# design.net
KiCad netlist of a schematic drawn in Altium Designer
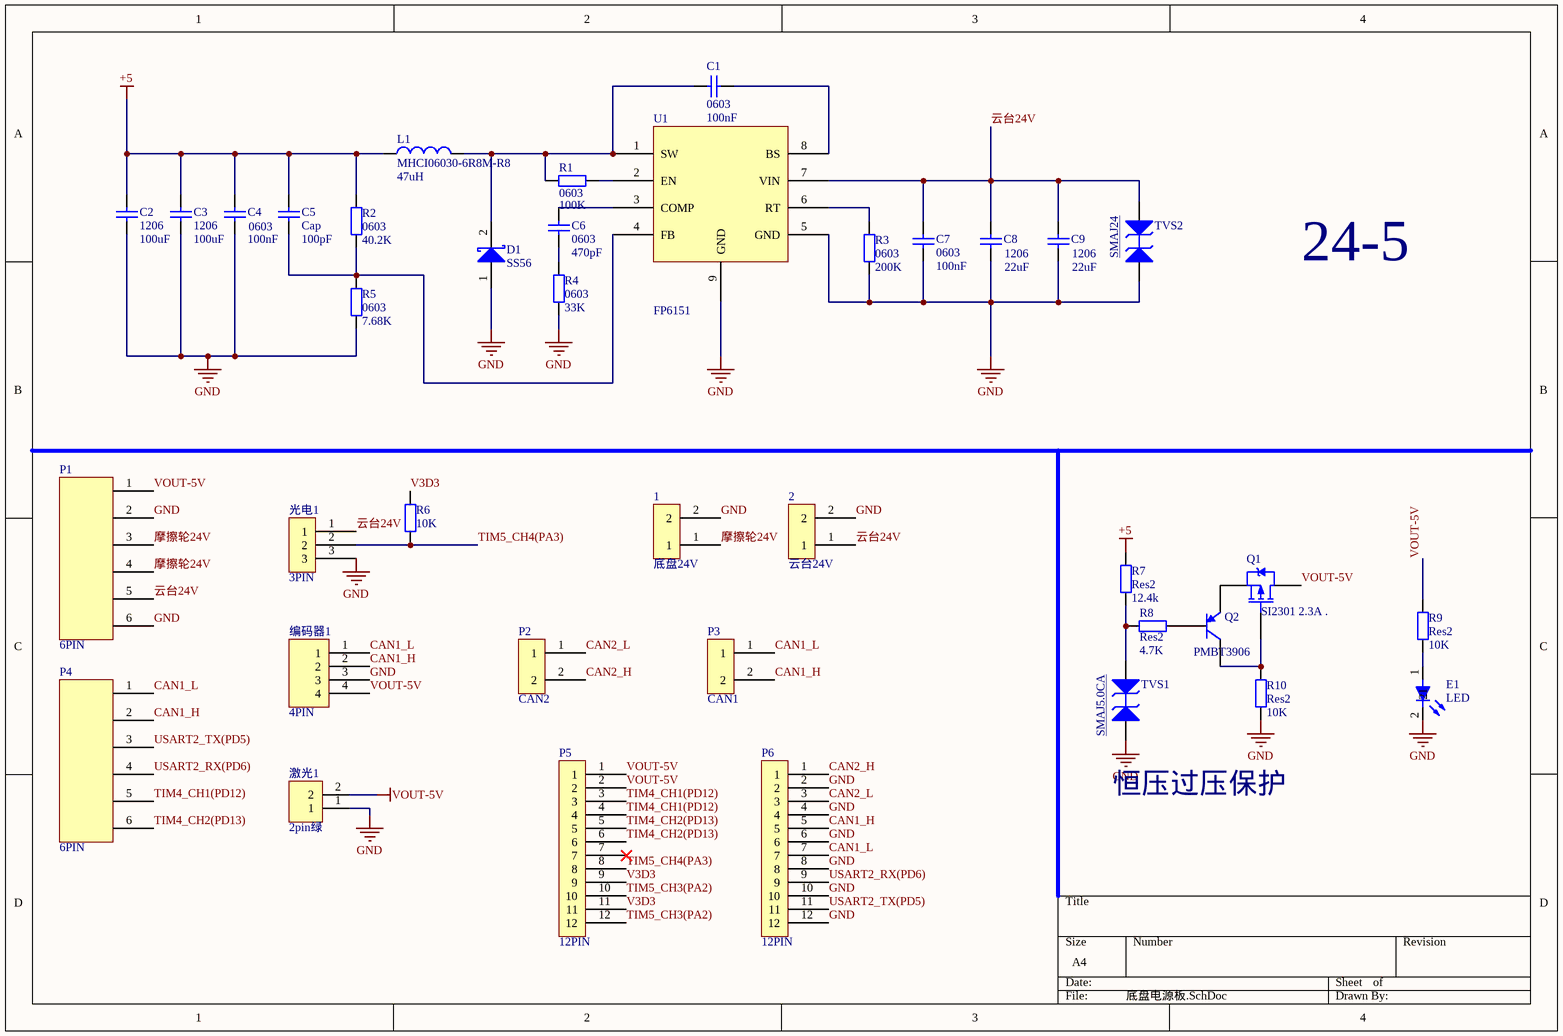
[diagram p0: 底盘电源板.SchDoc]

(export (version "E")
  (design (tool "Eeschema 10.0.6"))
  (components
    (comp (ref "1") (value "底盘24V") (footprint "XT30") (libsource (lib "PP_SCHlib_Altium") (part "2PIN")))
    (comp (ref "2") (value "云台24V") (footprint "XT30") (libsource (lib "PP_SCHlib_Altium") (part "2PIN")))
    (comp (ref "C1")
      (value "0603")
      (footprint "C0603")
      (description "Capacitor")
      (fields (field (name "0603") "100nF") (field (name "PUBLISHER") "Altium Limited"))
      (libsource (lib "Miscellaneous Devices") (part "Cap"))
    )
    (comp (ref "C2")
      (value "1206")
      (footprint "C1206")
      (description "Capacitor")
      (fields (field (name "ALTIUM_VALUE") "100uF") (field (name "PUBLISHER") "Altium Limited"))
      (libsource (lib "Miscellaneous Devices") (part "Cap"))
    )
    (comp (ref "C3")
      (value "1206")
      (footprint "C1206")
      (description "Capacitor")
      (fields (field (name "ALTIUM_VALUE") "100uF") (field (name "PUBLISHER") "Altium Limited"))
      (libsource (lib "Miscellaneous Devices") (part "Cap"))
    )
    (comp (ref "C4")
      (value "0603")
      (footprint "C0603")
      (description "Capacitor")
      (fields (field (name "ALTIUM_VALUE") "100nF") (field (name "PUBLISHER") "Altium Limited"))
      (libsource (lib "Miscellaneous Devices") (part "Cap"))
    )
    (comp (ref "C5")
      (value "Cap")
      (footprint "C0603")
      (description "Capacitor")
      (fields (field (name "ALTIUM_VALUE") "100pF") (field (name "PUBLISHER") "Altium Limited"))
      (libsource (lib "Miscellaneous Devices") (part "Cap"))
    )
    (comp (ref "C6")
      (value "0603")
      (footprint "C0603")
      (description "Capacitor")
      (fields (field (name "ALTIUM_VALUE") "470pF") (field (name "PUBLISHER") "Altium Limited"))
      (libsource (lib "Miscellaneous Devices") (part "Cap"))
    )
    (comp (ref "C7")
      (value "0603")
      (footprint "C0603")
      (description "Capacitor")
      (fields (field (name "0603") "100nF") (field (name "PUBLISHER") "Altium Limited"))
      (libsource (lib "Miscellaneous Devices") (part "Cap"))
    )
    (comp (ref "C8")
      (value "1206")
      (footprint "C1206")
      (description "Capacitor")
      (fields (field (name "ALTIUM_VALUE") "22uF") (field (name "PUBLISHER") "Altium Limited"))
      (libsource (lib "Miscellaneous Devices") (part "Cap"))
    )
    (comp (ref "C9")
      (value "1206")
      (footprint "C1206")
      (description "Capacitor")
      (fields (field (name "ALTIUM_VALUE") "22uF") (field (name "PUBLISHER") "Altium Limited"))
      (libsource (lib "Miscellaneous Devices") (part "Cap"))
    )
    (comp (ref "D1")
      (value "D-Schottky")
      (footprint "肖特基")
      (description "肖特基二极管")
      (fields (field (name "TYPE") "SS56") (field (name "PUBLISHER") "Altium Limited"))
      (libsource (lib "更多原理图库") (part "D-Schottky"))
    )
    (comp (ref "E1")
      (value "LED")
      (footprint "LED")
      (description "Typical RED, GREEN, YELLOW, AMBER GaAs LED")
      (fields (field (name "PUBLISHER") "Altium Limited"))
      (libsource (lib "PP_SCHlib_Altium") (part "LED"))
    )
    (comp (ref "L1")
      (value "MHCI06030-6R8M-R8")
      (footprint "L")
      (description "Inductor")
      (fields (field (name "ALTIUM_VALUE") "47uH") (field (name "PUBLISHER") "Altium Limited"))
      (libsource (lib "Miscellaneous Devices") (part "Inductor"))
    )
    (comp (ref "P1") (value "6PIN") (footprint "6PIN") (libsource (lib "PP_SCHlib_Altium") (part "6PIN")))
    (comp (ref "P2") (value "CAN2") (footprint "CAN") (libsource (lib "") (part "2PIN_1")))
    (comp (ref "P3") (value "CAN1") (footprint "CAN") (libsource (lib "") (part "2PIN_1")))
    (comp (ref "P4") (value "6PIN") (footprint "6PIN") (libsource (lib "PP_SCHlib_Altium") (part "6PIN")))
    (comp (ref "P5") (value "12PIN") (footprint "12pin") (libsource (lib "更多原理图库") (part "12PIN")))
    (comp (ref "P6") (value "12PIN") (footprint "12pin") (libsource (lib "更多原理图库") (part "12PIN")))
    (comp (ref "Q1")
      (value "SI2301 2.3A .")
      (footprint "SOT3")
      (description "P-Channel Power MOSFET")
      (fields (field (name "PUBLISHER") "Altium Limited"))
      (libsource (lib "Miscellaneous Devices") (part "PMOS-2"))
    )
    (comp (ref "Q2")
      (value "PMBT3906")
      (footprint "SOT3")
      (description "PNP Bipolar Transistor")
      (fields (field (name "PUBLISHER") "Altium Limited"))
      (libsource (lib "Miscellaneous Devices") (part "PNP"))
    )
    (comp (ref "R1")
      (value "0603")
      (footprint "R0603")
      (description "Resistor")
      (fields (field (name "0603") "100K") (field (name "PUBLISHER") "Altium Limited"))
      (libsource (lib "") (part "Res2_1"))
    )
    (comp (ref "R2")
      (value "0603")
      (footprint "R0603")
      (description "Resistor")
      (fields (field (name "ALTIUM_VALUE") "40.2K") (field (name "PUBLISHER") "Altium Limited"))
      (libsource (lib "Miscellaneous Devices") (part "Res2"))
    )
    (comp (ref "R3")
      (value "0603")
      (footprint "R0603")
      (description "Resistor")
      (fields (field (name "0603") "200K") (field (name "PUBLISHER") "Altium Limited"))
      (libsource (lib "Miscellaneous Devices") (part "Res2"))
    )
    (comp (ref "R4")
      (value "0603")
      (footprint "R0603")
      (description "Resistor")
      (fields (field (name "ALTIUM_VALUE") "33K") (field (name "PUBLISHER") "Altium Limited"))
      (libsource (lib "Miscellaneous Devices") (part "Res2"))
    )
    (comp (ref "R5")
      (value "0603")
      (footprint "R0603")
      (description "Resistor")
      (fields (field (name "ALTIUM_VALUE") "7.68K") (field (name "PUBLISHER") "Altium Limited"))
      (libsource (lib "Miscellaneous Devices") (part "Res2"))
    )
    (comp (ref "R6")
      (value "10K")
      (footprint "0805")
      (description "贴片电阻")
      (fields (field (name "Comment") "Res1") (field (name "PUBLISHER") "Altium Limited"))
      (libsource (lib "stm32test") (part "Res1"))
    )
    (comp (ref "R7")
      (value "Res2")
      (footprint "R0603")
      (description "Resistor")
      (fields (field (name "ALTIUM_VALUE") "12.4k") (field (name "PUBLISHER") "Altium Limited"))
      (libsource (lib "Miscellaneous Devices") (part "Res2"))
    )
    (comp (ref "R8")
      (value "Res2")
      (footprint "R0603")
      (description "Resistor")
      (fields (field (name "ALTIUM_VALUE") "4.7K") (field (name "PUBLISHER") "Altium Limited"))
      (libsource (lib "") (part "Res2_2"))
    )
    (comp (ref "R9")
      (value "Res2")
      (footprint "R0603")
      (description "Resistor")
      (fields (field (name "ALTIUM_VALUE") "10K") (field (name "PUBLISHER") "Altium Limited"))
      (libsource (lib "") (part "Res2_3"))
    )
    (comp (ref "R10")
      (value "Res2")
      (footprint "R0603")
      (description "Resistor")
      (fields (field (name "ALTIUM_VALUE") "10K") (field (name "PUBLISHER") "Altium Limited"))
      (libsource (lib "Miscellaneous Devices") (part "Res2"))
    )
    (comp (ref "TVS1")
      (value "SMAJ5.0CA")
      (footprint "SMAJ5.0")
      (libsource (lib "VL53L0X激光测距传感器模块") (part "TVS"))
    )
    (comp (ref "TVS2")
      (value "SMAJ24")
      (footprint "SMAJ24")
      (libsource (lib "VL53L0X激光测距传感器模块") (part "TVS"))
    )
    (comp (ref "U1") (value "FP6151") (footprint "FP") (libsource (lib "Schlib1") (part "FP6151")))
    (comp (ref "光电1") (value "3PIN") (footprint "光电") (libsource (lib "PP_SCHlib_Altium") (part "3PIN")))
    (comp (ref "激光1")
      (value "2pin绿")
      (footprint "2pin")
      (description "Molex-53261-0871")
      (fields (field (name "PUBLISHER") "Altium Limited"))
      (libsource (lib "通用板") (part "Molex-53398-0271"))
    )
    (comp (ref "编码器1") (value "4PIN") (footprint "编码器") (libsource (lib "PP_SCHlib_Altium") (part "4PIN")))
  )
  (nets
    (net (code "1") (name "+5") (class "Default")
      (node (ref "C2") (pin "2") (pinfunction "2_2") (pintype "passive"))
      (node (ref "C3") (pin "2") (pinfunction "2_2") (pintype "passive"))
      (node (ref "C4") (pin "2") (pinfunction "2_2") (pintype "passive"))
      (node (ref "C5") (pin "2") (pinfunction "2_2") (pintype "passive"))
      (node (ref "L1") (pin "1") (pinfunction "1_1") (pintype "passive"))
      (node (ref "R2") (pin "2") (pinfunction "2_2") (pintype "passive"))
      (node (ref "R7") (pin "2") (pinfunction "2_2") (pintype "passive"))
    )
    (net (code "2") (name "/CAN1_H") (class "Default")
      (node (ref "P3") (pin "2") (pinfunction "2_2") (pintype "passive"))
      (node (ref "P4") (pin "2") (pinfunction "2_2") (pintype "passive"))
      (node (ref "P6") (pin "5") (pinfunction "5_5") (pintype "passive"))
      (node (ref "编码器1") (pin "2") (pinfunction "2_2") (pintype "passive"))
    )
    (net (code "3") (name "/CAN1_L") (class "Default")
      (node (ref "P3") (pin "1") (pinfunction "1_1") (pintype "passive"))
      (node (ref "P4") (pin "1") (pinfunction "1_1") (pintype "passive"))
      (node (ref "P6") (pin "7") (pinfunction "7_7") (pintype "passive"))
      (node (ref "编码器1") (pin "1") (pinfunction "1_1") (pintype "passive"))
    )
    (net (code "4") (name "/CAN2_H") (class "Default")
      (node (ref "P2") (pin "2") (pinfunction "2_2") (pintype "passive"))
      (node (ref "P6") (pin "1") (pinfunction "1_1") (pintype "passive"))
    )
    (net (code "5") (name "/CAN2_L") (class "Default")
      (node (ref "P2") (pin "1") (pinfunction "1_1") (pintype "passive"))
      (node (ref "P6") (pin "3") (pinfunction "3_3") (pintype "passive"))
    )
    (net (code "6") (name "/TIM4_CH1(PD12)") (class "Default")
      (node (ref "P4") (pin "5") (pinfunction "5_5") (pintype "passive"))
      (node (ref "P5") (pin "3") (pinfunction "3_3") (pintype "passive"))
      (node (ref "P5") (pin "4") (pinfunction "4_4") (pintype "passive"))
    )
    (net (code "7") (name "/TIM4_CH2(PD13)") (class "Default")
      (node (ref "P4") (pin "6") (pinfunction "6_6") (pintype "passive"))
      (node (ref "P5") (pin "5") (pinfunction "5_5") (pintype "passive"))
      (node (ref "P5") (pin "6") (pinfunction "6_6") (pintype "passive"))
    )
    (net (code "8") (name "/TIM5_CH3(PA2)") (class "Default")
      (node (ref "P5") (pin "10") (pinfunction "10_10") (pintype "passive"))
      (node (ref "P5") (pin "12") (pinfunction "12_12") (pintype "passive"))
    )
    (net (code "9") (name "/TIM5_CH4(PA3)") (class "Default")
      (node (ref "P5") (pin "8") (pinfunction "8_8") (pintype "passive"))
      (node (ref "R6") (pin "1") (pinfunction "1_1") (pintype "passive"))
      (node (ref "光电1") (pin "2") (pinfunction "2_2") (pintype "passive"))
    )
    (net (code "10") (name "/USART2_RX(PD6)") (class "Default")
      (node (ref "P4") (pin "4") (pinfunction "4_4") (pintype "passive"))
      (node (ref "P6") (pin "9") (pinfunction "9_9") (pintype "passive"))
    )
    (net (code "11") (name "/USART2_TX(PD5)") (class "Default")
      (node (ref "P4") (pin "3") (pinfunction "3_3") (pintype "passive"))
      (node (ref "P6") (pin "11") (pinfunction "11_11") (pintype "passive"))
    )
    (net (code "12") (name "/V3D3") (class "Default")
      (node (ref "P5") (pin "11") (pinfunction "11_11") (pintype "passive"))
      (node (ref "P5") (pin "9") (pinfunction "9_9") (pintype "passive"))
      (node (ref "R6") (pin "2") (pinfunction "2_2") (pintype "passive"))
    )
    (net (code "13") (name "/云台24V") (class "Default")
      (node (ref "2") (pin "1") (pinfunction "1_1") (pintype "passive"))
      (node (ref "C7") (pin "2") (pinfunction "2_2") (pintype "passive"))
      (node (ref "C8") (pin "2") (pinfunction "2_2") (pintype "passive"))
      (node (ref "C9") (pin "2") (pinfunction "2_2") (pintype "passive"))
      (node (ref "P1") (pin "5") (pinfunction "5_5") (pintype "passive"))
      (node (ref "TVS2") (pin "2") (pinfunction "K_2") (pintype "passive"))
      (node (ref "U1") (pin "7") (pinfunction "VIN_7") (pintype "passive"))
      (node (ref "光电1") (pin "1") (pinfunction "1_1") (pintype "passive"))
    )
    (net (code "14") (name "/摩擦轮24V") (class "Default")
      (node (ref "1") (pin "1") (pinfunction "1_1") (pintype "passive"))
      (node (ref "P1") (pin "3") (pinfunction "3_3") (pintype "passive"))
      (node (ref "P1") (pin "4") (pinfunction "4_4") (pintype "passive"))
    )
    (net (code "15") (name "GND") (class "Default")
      (node (ref "1") (pin "2") (pinfunction "2_2") (pintype "passive"))
      (node (ref "2") (pin "2") (pinfunction "2_2") (pintype "passive"))
      (node (ref "C2") (pin "1") (pinfunction "1_1") (pintype "passive"))
      (node (ref "C3") (pin "1") (pinfunction "1_1") (pintype "passive"))
      (node (ref "C4") (pin "1") (pinfunction "1_1") (pintype "passive"))
      (node (ref "C7") (pin "1") (pinfunction "1_1") (pintype "passive"))
      (node (ref "C8") (pin "1") (pinfunction "1_1") (pintype "passive"))
      (node (ref "C9") (pin "1") (pinfunction "1_1") (pintype "passive"))
      (node (ref "D1") (pin "1") (pinfunction "A_1") (pintype "passive"))
      (node (ref "E1") (pin "2") (pinfunction "2_2") (pintype "passive"))
      (node (ref "P1") (pin "2") (pinfunction "2_2") (pintype "passive"))
      (node (ref "P1") (pin "6") (pinfunction "6_6") (pintype "passive"))
      (node (ref "P6") (pin "10") (pinfunction "10_10") (pintype "passive"))
      (node (ref "P6") (pin "12") (pinfunction "12_12") (pintype "passive"))
      (node (ref "P6") (pin "2") (pinfunction "2_2") (pintype "passive"))
      (node (ref "P6") (pin "4") (pinfunction "4_4") (pintype "passive"))
      (node (ref "P6") (pin "6") (pinfunction "6_6") (pintype "passive"))
      (node (ref "P6") (pin "8") (pinfunction "8_8") (pintype "passive"))
      (node (ref "R10") (pin "1") (pinfunction "1_1") (pintype "passive"))
      (node (ref "R3") (pin "1") (pinfunction "1_1") (pintype "passive"))
      (node (ref "R4") (pin "1") (pinfunction "1_1") (pintype "passive"))
      (node (ref "R5") (pin "1") (pinfunction "1_1") (pintype "passive"))
      (node (ref "TVS1") (pin "1") (pinfunction "A_1") (pintype "passive"))
      (node (ref "TVS2") (pin "1") (pinfunction "A_1") (pintype "passive"))
      (node (ref "U1") (pin "5") (pinfunction "GND_5") (pintype "passive"))
      (node (ref "U1") (pin "9") (pinfunction "GND_9") (pintype "passive"))
      (node (ref "光电1") (pin "3") (pinfunction "3_3") (pintype "passive"))
      (node (ref "激光1") (pin "1") (pinfunction "1_1") (pintype "passive"))
      (node (ref "编码器1") (pin "3") (pinfunction "3_3") (pintype "passive"))
    )
    (net (code "16") (name "Net-(C6-Pad1)") (class "Default")
      (node (ref "C6") (pin "1") (pinfunction "1_1") (pintype "passive"))
      (node (ref "R4") (pin "2") (pinfunction "2_2") (pintype "passive"))
    )
    (net (code "17") (name "Net-(D1-K)") (class "Default")
      (node (ref "C1") (pin "2") (pinfunction "2_2") (pintype "passive"))
      (node (ref "D1") (pin "2") (pinfunction "K_2") (pintype "passive"))
      (node (ref "L1") (pin "2") (pinfunction "2_2") (pintype "passive"))
      (node (ref "R1") (pin "2") (pinfunction "2_2") (pintype "passive"))
      (node (ref "U1") (pin "1") (pinfunction "SW_1") (pintype "passive"))
    )
    (net (code "18") (name "Net-(E1-Pad1)") (class "Default")
      (node (ref "E1") (pin "1") (pinfunction "1_1") (pintype "passive"))
      (node (ref "R9") (pin "2") (pinfunction "2_2") (pintype "passive"))
    )
    (net (code "19") (name "Net-(Q1-G)") (class "Default")
      (node (ref "Q1") (pin "1") (pinfunction "G_1") (pintype "passive"))
      (node (ref "Q2") (pin "3") (pinfunction "3_3") (pintype "passive"))
      (node (ref "R10") (pin "2") (pinfunction "2_2") (pintype "passive"))
    )
    (net (code "20") (name "Net-(Q1-s)") (class "Default")
      (node (ref "Q1") (pin "2") (pinfunction "s_2") (pintype "passive"))
      (node (ref "Q2") (pin "2") (pinfunction "2_2") (pintype "passive"))
    )
    (net (code "21") (name "Net-(Q2-Pad1)") (class "Default")
      (node (ref "Q2") (pin "1") (pinfunction "1_1") (pintype "passive"))
      (node (ref "R8") (pin "2") (pinfunction "2_2") (pintype "passive"))
    )
    (net (code "22") (name "Net-(TVS1-K)") (class "Default")
      (node (ref "R7") (pin "1") (pinfunction "1_1") (pintype "passive"))
      (node (ref "R8") (pin "1") (pinfunction "1_1") (pintype "passive"))
      (node (ref "TVS1") (pin "2") (pinfunction "K_2") (pintype "passive"))
    )
    (net (code "23") (name "Net-(U1-BS)") (class "Default")
      (node (ref "C1") (pin "1") (pinfunction "1_1") (pintype "passive"))
      (node (ref "U1") (pin "8") (pinfunction "BS_8") (pintype "passive"))
    )
    (net (code "24") (name "Net-(U1-COMP)") (class "Default")
      (node (ref "C6") (pin "2") (pinfunction "2_2") (pintype "passive"))
      (node (ref "U1") (pin "3") (pinfunction "COMP_3") (pintype "passive"))
    )
    (net (code "25") (name "Net-(U1-EN)") (class "Default")
      (node (ref "R1") (pin "1") (pinfunction "1_1") (pintype "passive"))
      (node (ref "U1") (pin "2") (pinfunction "EN_2") (pintype "passive"))
    )
    (net (code "26") (name "Net-(U1-FB)") (class "Default")
      (node (ref "C5") (pin "1") (pinfunction "1_1") (pintype "passive"))
      (node (ref "R2") (pin "1") (pinfunction "1_1") (pintype "passive"))
      (node (ref "R5") (pin "2") (pinfunction "2_2") (pintype "passive"))
      (node (ref "U1") (pin "4") (pinfunction "FB_4") (pintype "passive"))
    )
    (net (code "27") (name "Net-(U1-RT)") (class "Default")
      (node (ref "R3") (pin "2") (pinfunction "2_2") (pintype "passive"))
      (node (ref "U1") (pin "6") (pinfunction "RT_6") (pintype "passive"))
    )
    (net (code "28") (name "VOUT-5V") (class "Default")
      (node (ref "P1") (pin "1") (pinfunction "1_1") (pintype "passive"))
      (node (ref "P5") (pin "1") (pinfunction "1_1") (pintype "passive"))
      (node (ref "P5") (pin "2") (pinfunction "2_2") (pintype "passive"))
      (node (ref "Q1") (pin "3") (pinfunction "D_3") (pintype "passive"))
      (node (ref "R9") (pin "1") (pinfunction "1_1") (pintype "passive"))
      (node (ref "激光1") (pin "2") (pinfunction "2_2") (pintype "passive"))
      (node (ref "编码器1") (pin "4") (pinfunction "4_4") (pintype "passive"))
    )
    (net (code "29") (name "unconnected-(P5-Pad7)") (class "Default")
      (node (ref "P5") (pin "7") (pinfunction "7_7") (pintype "passive+no_connect"))
    )
  )
)
